# LoRaSocket.net
KiCad netlist of a schematic drawn in Altium Designer
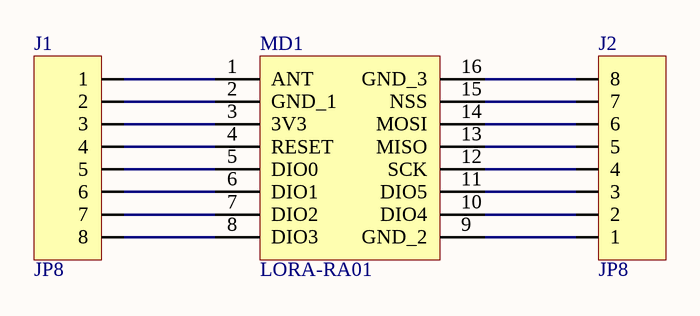
[diagram p0: LoRaSocket.SchDoc]

(export (version "E")
  (design (tool "Eeschema 10.0.6"))
  (components
    (comp (ref "J1")
      (value "JP8")
      (footprint "JP8-D1T")
      (description "WR-PHD 2.54 mm Angled Socket Header")
      (fields
        (field (name "MANUFACTURER") "Würth Elektronik eiSos GmbH")
        (field (name "PARTNO") "613008143121")
        (field (name "CREATED BY") "Karrer Zheng")
      )
      (libsource (lib "LIBRARY") (part "JP8"))
    )
    (comp (ref "J2")
      (value "JP8")
      (footprint "JP8-D1T")
      (description "WR-PHD 2.54 mm Angled Socket Header")
      (fields
        (field (name "MANUFACTURER") "Würth Elektronik eiSos GmbH")
        (field (name "PARTNO") "613008143121")
        (field (name "CREATED BY") "Karrer Zheng")
      )
      (libsource (lib "") (part "JP8_1"))
    )
    (comp (ref "MD1")
      (value "LORA-RA01")
      (footprint "LORA-RA01")
      (description "Module LoRa RA-01 SX1278")
      (libsource (lib "phatvu1294_Lib") (part "LORA-RA01"))
    )
  )
  (nets
    (net (code "1") (name "Net-(MD1-3V3)") (class "Default")
      (node (ref "J1") (pin "3") (pinfunction "3_3") (pintype "passive"))
      (node (ref "MD1") (pin "3") (pinfunction "3V3_3") (pintype "passive"))
    )
    (net (code "2") (name "Net-(MD1-ANT)") (class "Default")
      (node (ref "J1") (pin "1") (pinfunction "1_1") (pintype "passive"))
      (node (ref "MD1") (pin "1") (pinfunction "ANT_1") (pintype "passive"))
    )
    (net (code "3") (name "Net-(MD1-DIO0)") (class "Default")
      (node (ref "J1") (pin "5") (pinfunction "5_5") (pintype "passive"))
      (node (ref "MD1") (pin "5") (pinfunction "DIO0_5") (pintype "passive"))
    )
    (net (code "4") (name "Net-(MD1-DIO1)") (class "Default")
      (node (ref "J1") (pin "6") (pinfunction "6_6") (pintype "passive"))
      (node (ref "MD1") (pin "6") (pinfunction "DIO1_6") (pintype "passive"))
    )
    (net (code "5") (name "Net-(MD1-DIO2)") (class "Default")
      (node (ref "J1") (pin "7") (pinfunction "7_7") (pintype "passive"))
      (node (ref "MD1") (pin "7") (pinfunction "DIO2_7") (pintype "passive"))
    )
    (net (code "6") (name "Net-(MD1-DIO3)") (class "Default")
      (node (ref "J1") (pin "8") (pinfunction "8_8") (pintype "passive"))
      (node (ref "MD1") (pin "8") (pinfunction "DIO3_8") (pintype "passive"))
    )
    (net (code "7") (name "Net-(MD1-DIO4)") (class "Default")
      (node (ref "J2") (pin "2") (pinfunction "2_2") (pintype "passive"))
      (node (ref "MD1") (pin "10") (pinfunction "DIO4_10") (pintype "passive"))
    )
    (net (code "8") (name "Net-(MD1-DIO5)") (class "Default")
      (node (ref "J2") (pin "3") (pinfunction "3_3") (pintype "passive"))
      (node (ref "MD1") (pin "11") (pinfunction "DIO5_11") (pintype "passive"))
    )
    (net (code "9") (name "Net-(MD1-GND_1)") (class "Default")
      (node (ref "J1") (pin "2") (pinfunction "2_2") (pintype "passive"))
      (node (ref "MD1") (pin "2") (pinfunction "GND_1_2") (pintype "passive"))
    )
    (net (code "10") (name "Net-(MD1-GND_2)") (class "Default")
      (node (ref "J2") (pin "1") (pinfunction "1_1") (pintype "passive"))
      (node (ref "MD1") (pin "9") (pinfunction "GND_2_9") (pintype "passive"))
    )
    (net (code "11") (name "Net-(MD1-GND_3)") (class "Default")
      (node (ref "J2") (pin "8") (pinfunction "8_8") (pintype "passive"))
      (node (ref "MD1") (pin "16") (pinfunction "GND_3_16") (pintype "passive"))
    )
    (net (code "12") (name "Net-(MD1-MISO)") (class "Default")
      (node (ref "J2") (pin "5") (pinfunction "5_5") (pintype "passive"))
      (node (ref "MD1") (pin "13") (pinfunction "MISO_13") (pintype "passive"))
    )
    (net (code "13") (name "Net-(MD1-MOSI)") (class "Default")
      (node (ref "J2") (pin "6") (pinfunction "6_6") (pintype "passive"))
      (node (ref "MD1") (pin "14") (pinfunction "MOSI_14") (pintype "passive"))
    )
    (net (code "14") (name "Net-(MD1-NSS)") (class "Default")
      (node (ref "J2") (pin "7") (pinfunction "7_7") (pintype "passive"))
      (node (ref "MD1") (pin "15") (pinfunction "NSS_15") (pintype "passive"))
    )
    (net (code "15") (name "Net-(MD1-RESET)") (class "Default")
      (node (ref "J1") (pin "4") (pinfunction "4_4") (pintype "passive"))
      (node (ref "MD1") (pin "4") (pinfunction "RESET_4") (pintype "passive"))
    )
    (net (code "16") (name "Net-(MD1-SCK)") (class "Default")
      (node (ref "J2") (pin "4") (pinfunction "4_4") (pintype "passive"))
      (node (ref "MD1") (pin "12") (pinfunction "SCK_12") (pintype "passive"))
    )
  )
)
